# six_max_uno_2021-06-03.net
KiCad netlist of a schematic drawn in EasyEDA
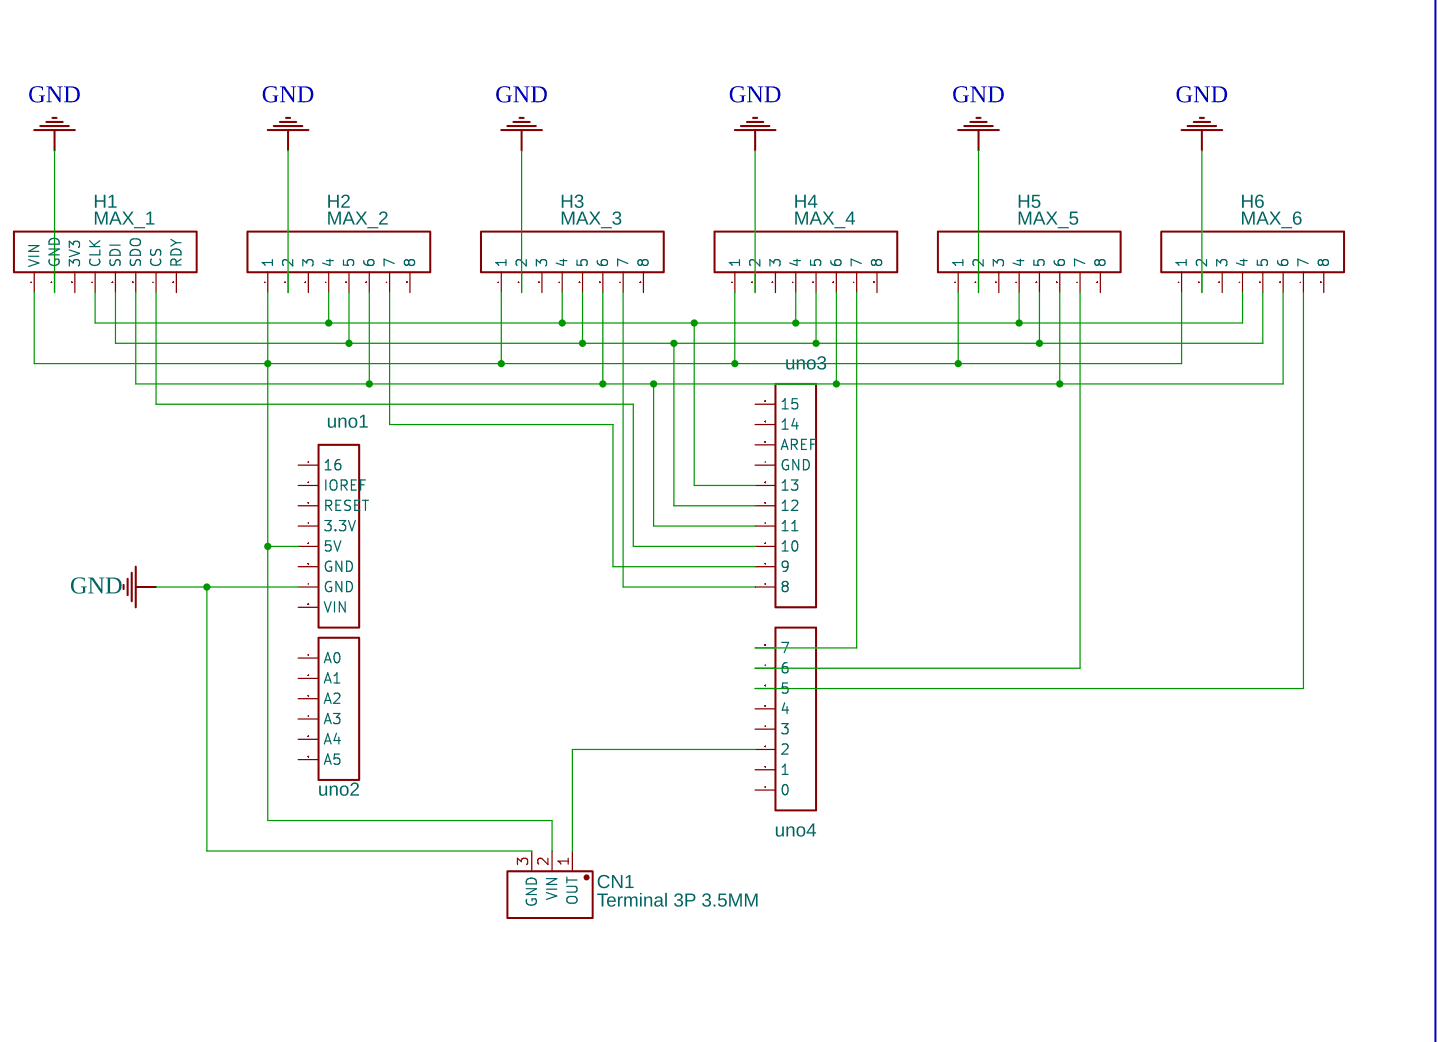
[diagram p0: schematic sheet]

(export (version "E")
  (design (tool "Eeschema 10.0.6"))
  (components
    (comp (ref "CN1")
      (value "Terminal 3P 3.5MM")
      (fields (field (name "BOM_Manufacturer Part") "31524103") (field (name "BOM_Supplier Part") "C123243"))
      (libsource (lib "") (part "Terminal 3P 3.5MM"))
    )
    (comp (ref "H1")
      (value "MAX_1")
      (fields (field (name "BOM_Supplier Part") "C225505"))
      (libsource (lib "") (part "HDR-F-2.54_1x8_1"))
    )
    (comp (ref "H2")
      (value "MAX_2")
      (fields (field (name "BOM_Supplier Part") "C225505"))
      (libsource (lib "") (part "HDR-F-2.54_1x8"))
    )
    (comp (ref "H3")
      (value "MAX_3")
      (fields (field (name "BOM_Supplier Part") "C225505"))
      (libsource (lib "") (part "HDR-F-2.54_1x8"))
    )
    (comp (ref "H4")
      (value "MAX_4")
      (fields (field (name "BOM_Supplier Part") "C225505"))
      (libsource (lib "") (part "HDR-F-2.54_1x8"))
    )
    (comp (ref "H5")
      (value "MAX_5")
      (fields (field (name "BOM_Supplier Part") "C225505"))
      (libsource (lib "") (part "HDR-F-2.54_1x8"))
    )
    (comp (ref "H6")
      (value "MAX_6")
      (fields (field (name "BOM_Supplier Part") "C225505"))
      (libsource (lib "") (part "HDR-F-2.54_1x8"))
    )
    (comp (ref "J1")
      (value "uno4")
      (fields (field (name "BOM_Supplier Part") "C190820"))
      (libsource (lib "") (part "HDR-M-2.54_1x8"))
    )
    (comp (ref "J2")
      (value "uno1")
      (fields (field (name "BOM_Supplier Part") "C190820"))
      (libsource (lib "") (part "HDR-M-2.54_1x8_1"))
    )
    (comp (ref "J3")
      (value "uno3")
      (fields (field (name "BOM_Supplier Part") "C57369"))
      (libsource (lib "") (part "HDR-M-2.54_1x10"))
    )
    (comp (ref "J4")
      (value "uno2")
      (fields (field (name "BOM_Supplier Part") "C190819"))
      (libsource (lib "") (part "HDR-M-2.54_1x6"))
    )
  )
  (nets
    (net (code "1") (name "GND") (class "Default")
      (node (ref "CN1") (pin "3") (pinfunction "GND_3") (pintype "unspecified"))
      (node (ref "H1") (pin "2") (pinfunction "GND_2") (pintype "unspecified"))
      (node (ref "H2") (pin "2") (pinfunction "2_2") (pintype "unspecified"))
      (node (ref "H3") (pin "2") (pinfunction "2_2") (pintype "unspecified"))
      (node (ref "H4") (pin "2") (pinfunction "2_2") (pintype "unspecified"))
      (node (ref "H5") (pin "2") (pinfunction "2_2") (pintype "unspecified"))
      (node (ref "H6") (pin "2") (pinfunction "2_2") (pintype "unspecified"))
      (node (ref "J2") (pin "7") (pinfunction "GND_7") (pintype "unspecified"))
    )
    (net (code "2") (name "Net-(CN1-OUT)") (class "Default")
      (node (ref "CN1") (pin "1") (pinfunction "OUT_1") (pintype "unspecified"))
      (node (ref "J1") (pin "3") (pinfunction "2_3") (pintype "unspecified"))
    )
    (net (code "3") (name "Net-(CN1-VIN)") (class "Default")
      (node (ref "CN1") (pin "2") (pinfunction "VIN_2") (pintype "unspecified"))
      (node (ref "H1") (pin "1") (pinfunction "VIN_1") (pintype "unspecified"))
      (node (ref "H2") (pin "1") (pinfunction "1_1") (pintype "unspecified"))
      (node (ref "H3") (pin "1") (pinfunction "1_1") (pintype "unspecified"))
      (node (ref "H4") (pin "1") (pinfunction "1_1") (pintype "unspecified"))
      (node (ref "H5") (pin "1") (pinfunction "1_1") (pintype "unspecified"))
      (node (ref "H6") (pin "1") (pinfunction "1_1") (pintype "unspecified"))
      (node (ref "J2") (pin "5") (pinfunction "5V_5") (pintype "unspecified"))
    )
    (net (code "4") (name "Net-(H1-CLK)") (class "Default")
      (node (ref "H1") (pin "4") (pinfunction "CLK_4") (pintype "unspecified"))
      (node (ref "H2") (pin "4") (pinfunction "4_4") (pintype "unspecified"))
      (node (ref "H3") (pin "4") (pinfunction "4_4") (pintype "unspecified"))
      (node (ref "H4") (pin "4") (pinfunction "4_4") (pintype "unspecified"))
      (node (ref "H5") (pin "4") (pinfunction "4_4") (pintype "unspecified"))
      (node (ref "H6") (pin "4") (pinfunction "4_4") (pintype "unspecified"))
      (node (ref "J3") (pin "6") (pinfunction "13_6") (pintype "unspecified"))
    )
    (net (code "5") (name "Net-(H1-CS)") (class "Default")
      (node (ref "H1") (pin "7") (pinfunction "CS_7") (pintype "unspecified"))
      (node (ref "J3") (pin "3") (pinfunction "10_3") (pintype "unspecified"))
    )
    (net (code "6") (name "Net-(H1-SDI)") (class "Default")
      (node (ref "H1") (pin "5") (pinfunction "SDI_5") (pintype "unspecified"))
      (node (ref "H2") (pin "5") (pinfunction "5_5") (pintype "unspecified"))
      (node (ref "H3") (pin "5") (pinfunction "5_5") (pintype "unspecified"))
      (node (ref "H4") (pin "5") (pinfunction "5_5") (pintype "unspecified"))
      (node (ref "H5") (pin "5") (pinfunction "5_5") (pintype "unspecified"))
      (node (ref "H6") (pin "5") (pinfunction "5_5") (pintype "unspecified"))
      (node (ref "J3") (pin "5") (pinfunction "12_5") (pintype "unspecified"))
    )
    (net (code "7") (name "Net-(H1-SDO)") (class "Default")
      (node (ref "H1") (pin "6") (pinfunction "SDO_6") (pintype "unspecified"))
      (node (ref "H2") (pin "6") (pinfunction "6_6") (pintype "unspecified"))
      (node (ref "H3") (pin "6") (pinfunction "6_6") (pintype "unspecified"))
      (node (ref "H4") (pin "6") (pinfunction "6_6") (pintype "unspecified"))
      (node (ref "H5") (pin "6") (pinfunction "6_6") (pintype "unspecified"))
      (node (ref "H6") (pin "6") (pinfunction "6_6") (pintype "unspecified"))
      (node (ref "J3") (pin "4") (pinfunction "11_4") (pintype "unspecified"))
    )
    (net (code "8") (name "Net-(J1-5)") (class "Default")
      (node (ref "H6") (pin "7") (pinfunction "7_7") (pintype "unspecified"))
      (node (ref "J1") (pin "6") (pinfunction "5_6") (pintype "unspecified"))
    )
    (net (code "9") (name "Net-(J1-6)") (class "Default")
      (node (ref "H5") (pin "7") (pinfunction "7_7") (pintype "unspecified"))
      (node (ref "J1") (pin "7") (pinfunction "6_7") (pintype "unspecified"))
    )
    (net (code "10") (name "Net-(J1-7)") (class "Default")
      (node (ref "H4") (pin "7") (pinfunction "7_7") (pintype "unspecified"))
      (node (ref "J1") (pin "8") (pinfunction "7_8") (pintype "unspecified"))
    )
    (net (code "11") (name "Net-(J3-8)") (class "Default")
      (node (ref "H3") (pin "7") (pinfunction "7_7") (pintype "unspecified"))
      (node (ref "J3") (pin "1") (pinfunction "8_1") (pintype "unspecified"))
    )
    (net (code "12") (name "Net-(J3-9)") (class "Default")
      (node (ref "H2") (pin "7") (pinfunction "7_7") (pintype "unspecified"))
      (node (ref "J3") (pin "2") (pinfunction "9_2") (pintype "unspecified"))
    )
    (net (code "13") (name "unconnected-(H1-3V3-Pad3)") (class "Default")
      (node (ref "H1") (pin "3") (pinfunction "3V3_3") (pintype "unspecified"))
    )
    (net (code "14") (name "unconnected-(H1-RDY-Pad8)") (class "Default")
      (node (ref "H1") (pin "8") (pinfunction "RDY_8") (pintype "unspecified"))
    )
    (net (code "15") (name "unconnected-(H2-Pad3)") (class "Default")
      (node (ref "H2") (pin "3") (pinfunction "3_3") (pintype "unspecified"))
    )
    (net (code "16") (name "unconnected-(H2-Pad8)") (class "Default")
      (node (ref "H2") (pin "8") (pinfunction "8_8") (pintype "unspecified"))
    )
    (net (code "17") (name "unconnected-(H3-Pad3)") (class "Default")
      (node (ref "H3") (pin "3") (pinfunction "3_3") (pintype "unspecified"))
    )
    (net (code "18") (name "unconnected-(H3-Pad8)") (class "Default")
      (node (ref "H3") (pin "8") (pinfunction "8_8") (pintype "unspecified"))
    )
    (net (code "19") (name "unconnected-(H4-Pad3)") (class "Default")
      (node (ref "H4") (pin "3") (pinfunction "3_3") (pintype "unspecified"))
    )
    (net (code "20") (name "unconnected-(H4-Pad8)") (class "Default")
      (node (ref "H4") (pin "8") (pinfunction "8_8") (pintype "unspecified"))
    )
    (net (code "21") (name "unconnected-(H5-Pad3)") (class "Default")
      (node (ref "H5") (pin "3") (pinfunction "3_3") (pintype "unspecified"))
    )
    (net (code "22") (name "unconnected-(H5-Pad8)") (class "Default")
      (node (ref "H5") (pin "8") (pinfunction "8_8") (pintype "unspecified"))
    )
    (net (code "23") (name "unconnected-(H6-Pad3)") (class "Default")
      (node (ref "H6") (pin "3") (pinfunction "3_3") (pintype "unspecified"))
    )
    (net (code "24") (name "unconnected-(H6-Pad8)") (class "Default")
      (node (ref "H6") (pin "8") (pinfunction "8_8") (pintype "unspecified"))
    )
    (net (code "25") (name "unconnected-(J1-0-Pad1)") (class "Default")
      (node (ref "J1") (pin "1") (pinfunction "0_1") (pintype "unspecified"))
    )
    (net (code "26") (name "unconnected-(J1-1-Pad2)") (class "Default")
      (node (ref "J1") (pin "2") (pinfunction "1_2") (pintype "unspecified"))
    )
    (net (code "27") (name "unconnected-(J1-3-Pad4)") (class "Default")
      (node (ref "J1") (pin "4") (pinfunction "3_4") (pintype "unspecified"))
    )
    (net (code "28") (name "unconnected-(J1-4-Pad5)") (class "Default")
      (node (ref "J1") (pin "5") (pinfunction "4_5") (pintype "unspecified"))
    )
    (net (code "29") (name "unconnected-(J2-3.3V-Pad4)") (class "Default")
      (node (ref "J2") (pin "4") (pinfunction "3.3V_4") (pintype "unspecified"))
    )
    (net (code "30") (name "unconnected-(J2-16-Pad1)") (class "Default")
      (node (ref "J2") (pin "1") (pinfunction "16_1") (pintype "unspecified"))
    )
    (net (code "31") (name "unconnected-(J2-GND-Pad6)") (class "Default")
      (node (ref "J2") (pin "6") (pinfunction "GND_6") (pintype "unspecified"))
    )
    (net (code "32") (name "unconnected-(J2-IOREF-Pad2)") (class "Default")
      (node (ref "J2") (pin "2") (pinfunction "IOREF_2") (pintype "unspecified"))
    )
    (net (code "33") (name "unconnected-(J2-RESET-Pad3)") (class "Default")
      (node (ref "J2") (pin "3") (pinfunction "RESET_3") (pintype "unspecified"))
    )
    (net (code "34") (name "unconnected-(J2-VIN-Pad8)") (class "Default")
      (node (ref "J2") (pin "8") (pinfunction "VIN_8") (pintype "unspecified"))
    )
    (net (code "35") (name "unconnected-(J3-14-Pad9)") (class "Default")
      (node (ref "J3") (pin "9") (pinfunction "14_9") (pintype "unspecified"))
    )
    (net (code "36") (name "unconnected-(J3-15-Pad10)") (class "Default")
      (node (ref "J3") (pin "10") (pinfunction "15_10") (pintype "unspecified"))
    )
    (net (code "37") (name "unconnected-(J3-AREF-Pad8)") (class "Default")
      (node (ref "J3") (pin "8") (pinfunction "AREF_8") (pintype "unspecified"))
    )
    (net (code "38") (name "unconnected-(J3-GND-Pad7)") (class "Default")
      (node (ref "J3") (pin "7") (pinfunction "GND_7") (pintype "unspecified"))
    )
    (net (code "39") (name "unconnected-(J4-A0-Pad1)") (class "Default")
      (node (ref "J4") (pin "1") (pinfunction "A0_1") (pintype "input"))
    )
    (net (code "40") (name "unconnected-(J4-A1-Pad2)") (class "Default")
      (node (ref "J4") (pin "2") (pinfunction "A1_2") (pintype "input"))
    )
    (net (code "41") (name "unconnected-(J4-A2-Pad3)") (class "Default")
      (node (ref "J4") (pin "3") (pinfunction "A2_3") (pintype "input"))
    )
    (net (code "42") (name "unconnected-(J4-A3-Pad4)") (class "Default")
      (node (ref "J4") (pin "4") (pinfunction "A3_4") (pintype "input"))
    )
    (net (code "43") (name "unconnected-(J4-A4-Pad5)") (class "Default")
      (node (ref "J4") (pin "5") (pinfunction "A4_5") (pintype "input"))
    )
    (net (code "44") (name "unconnected-(J4-A5-Pad6)") (class "Default")
      (node (ref "J4") (pin "6") (pinfunction "A5_6") (pintype "input"))
    )
  )
)
